# schematic.net
KiCad netlist of a schematic drawn in EAGLE
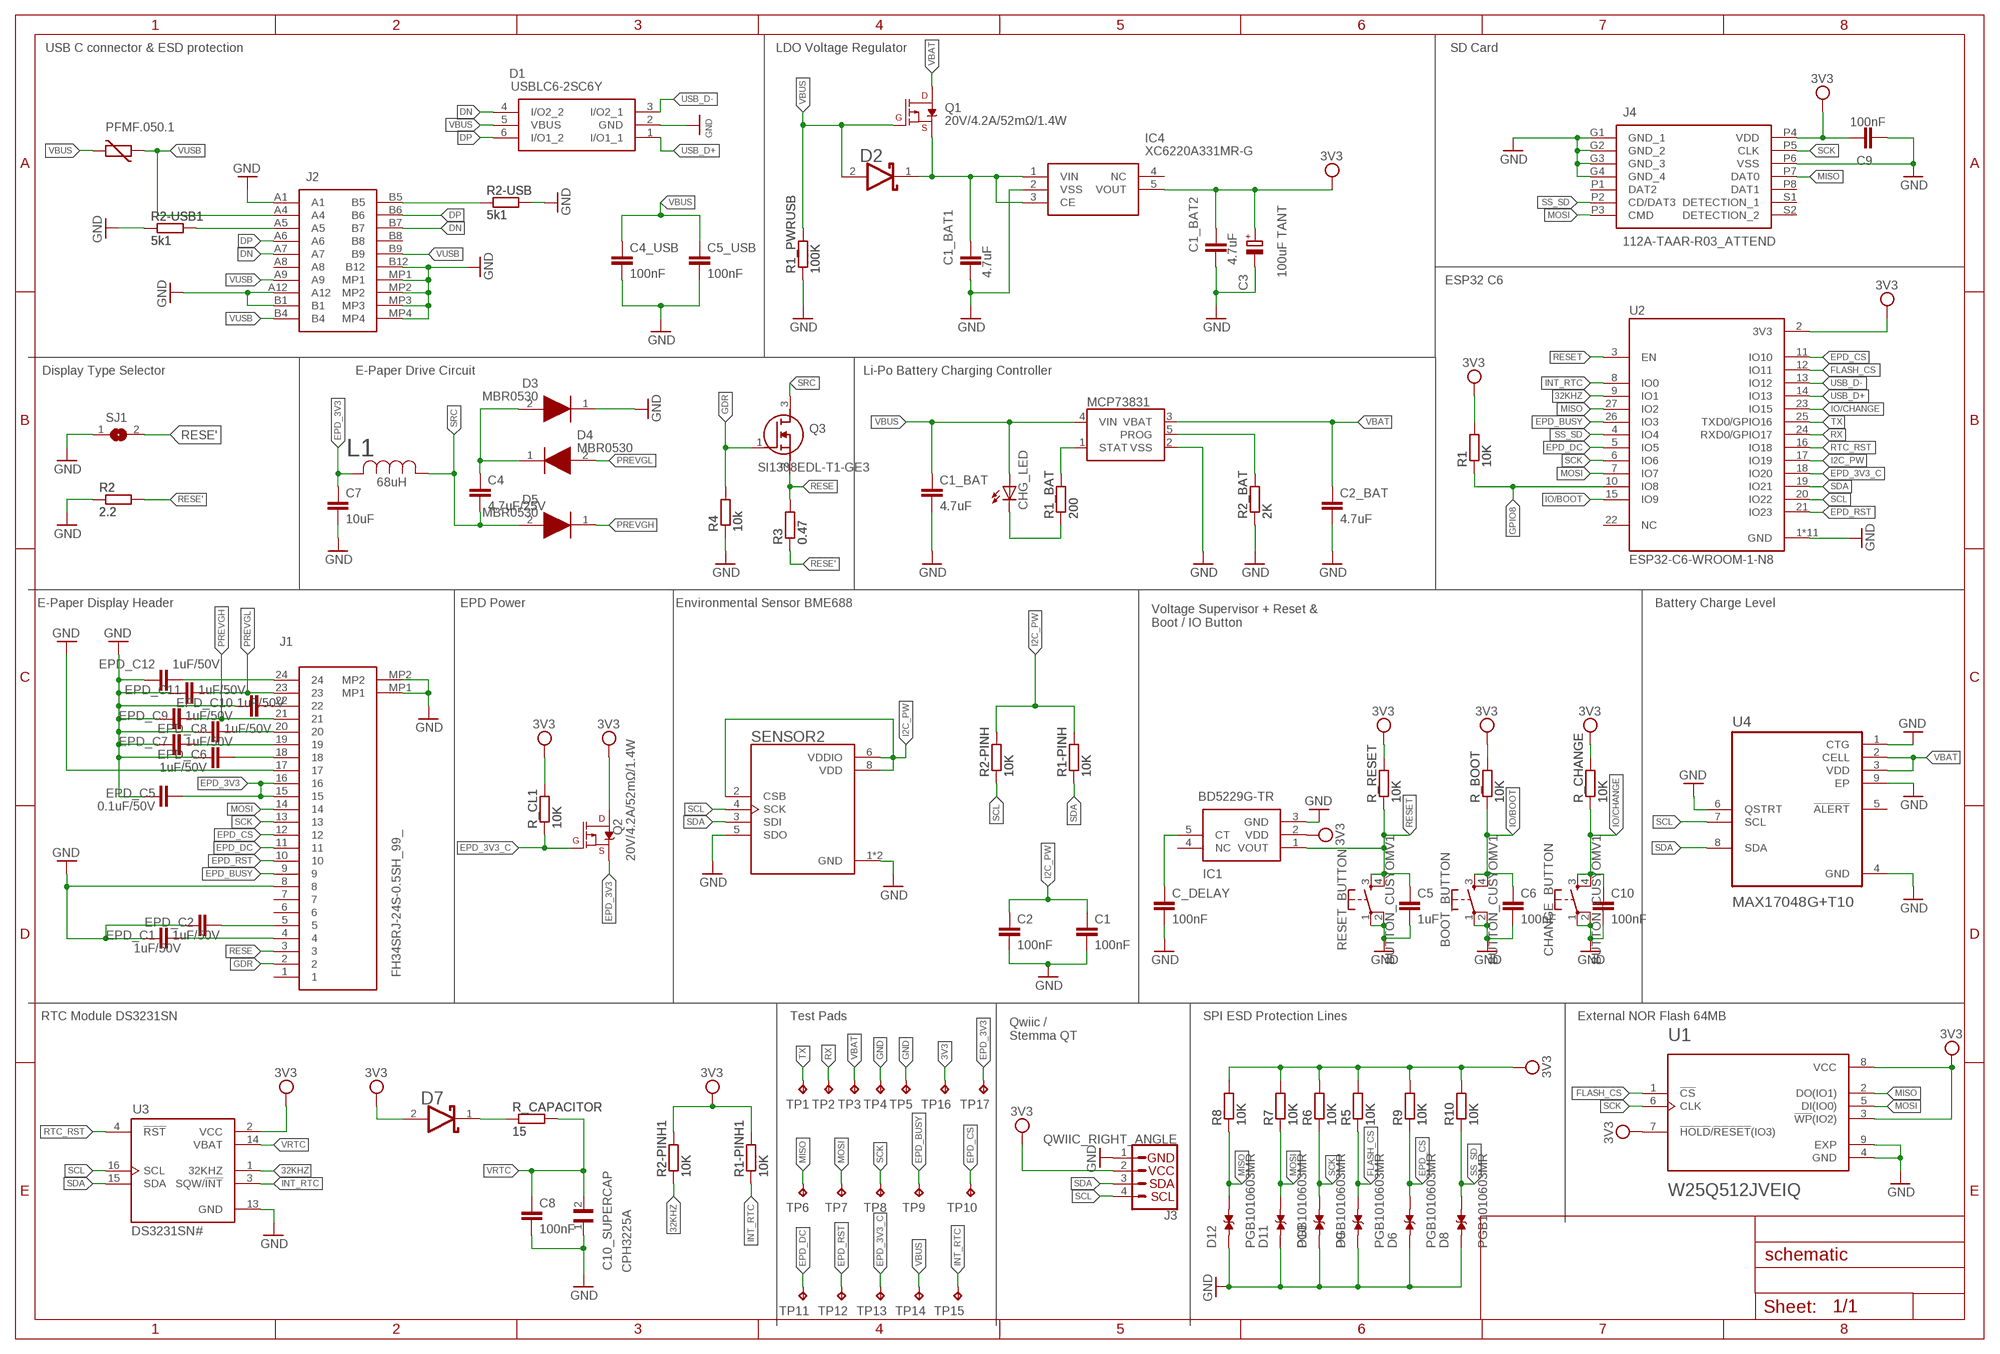
[diagram p0: schematic, sheet 1]

(export (version "E")
  (design (tool "Eeschema 10.0.6"))
  (components
    (comp (ref "BOOT_BUTTON")
      (value "BUTTON_CUSYOMV1")
      (footprint "eagle-import:MYBUTTON")
      (libsource (lib "eagle-import") (part "BUTTON_CUSYOMV1"))
    )
    (comp (ref "C1")
      (value "100nF")
      (footprint "eagle-import:ESP32_WROVER_EAGLE-LTSPICE_C0402")
      (libsource (lib "eagle-import") (part "ESP32_WROVER_EAGLE-LTSPICE_CC0402"))
    )
    (comp (ref "C1_BAT")
      (value "4.7uF")
      (footprint "eagle-import:ESP32_WROVER_EAGLE-LTSPICE_C0402")
      (libsource (lib "eagle-import") (part "ESP32_WROVER_EAGLE-LTSPICE_CC0402"))
    )
    (comp (ref "C1_BAT1")
      (value "4.7uF")
      (footprint "eagle-import:ESP32_WROVER_EAGLE-LTSPICE_C0402")
      (libsource (lib "eagle-import") (part "EAGLE-LTSPICE_CC0402"))
    )
    (comp (ref "C1_BAT2")
      (value "4.7uF")
      (footprint "eagle-import:ESP32_WROVER_EAGLE-LTSPICE_C0402")
      (libsource (lib "eagle-import") (part "EAGLE-LTSPICE_CC0402"))
    )
    (comp (ref "C2")
      (value "100nF")
      (footprint "eagle-import:ESP32_WROVER_EAGLE-LTSPICE_C0402")
      (libsource (lib "eagle-import") (part "ESP32_WROVER_EAGLE-LTSPICE_CC0402"))
    )
    (comp (ref "C2_BAT")
      (value "4.7uF")
      (footprint "eagle-import:ESP32_WROVER_EAGLE-LTSPICE_C0402")
      (libsource (lib "eagle-import") (part "ESP32_WROVER_EAGLE-LTSPICE_CC0402"))
    )
    (comp (ref "C3")
      (value "100uF TANT")
      (footprint "eagle-import:RCL_CT3528")
      (libsource (lib "eagle-import") (part "RCL_CPOL-EUCT3528"))
    )
    (comp (ref "C4")
      (value "4.7uF/25V")
      (footprint "eagle-import:ESP32_WROVER_EAGLE-LTSPICE_C0402")
      (libsource (lib "eagle-import") (part "ESP32_WROVER_EAGLE-LTSPICE_CC0402"))
    )
    (comp (ref "C4_USB")
      (value "100nF")
      (footprint "eagle-import:ESP32_WROVER_EAGLE-LTSPICE_C0402")
      (libsource (lib "eagle-import") (part "ESP32_WROVER_EAGLE-LTSPICE_CC0402"))
    )
    (comp (ref "C5")
      (value "1uF")
      (footprint "eagle-import:ESP32_WROVER_EAGLE-LTSPICE_C0402")
      (libsource (lib "eagle-import") (part "ESP32_WROVER_EAGLE-LTSPICE_CC0402"))
    )
    (comp (ref "C5_USB")
      (value "100nF")
      (footprint "eagle-import:ESP32_WROVER_EAGLE-LTSPICE_C0402")
      (libsource (lib "eagle-import") (part "ESP32_WROVER_EAGLE-LTSPICE_CC0402"))
    )
    (comp (ref "C6")
      (value "100nF")
      (footprint "eagle-import:ESP32_WROVER_EAGLE-LTSPICE_C0402")
      (libsource (lib "eagle-import") (part "ESP32_WROVER_EAGLE-LTSPICE_CC0402"))
    )
    (comp (ref "C7")
      (value "10uF")
      (footprint "eagle-import:ESP32_WROVER_EAGLE-LTSPICE_C0402")
      (libsource (lib "eagle-import") (part "ESP32_WROVER_EAGLE-LTSPICE_CC0402"))
    )
    (comp (ref "C8")
      (value "100nF")
      (footprint "eagle-import:ESP32_WROVER_EAGLE-LTSPICE_C0402")
      (libsource (lib "eagle-import") (part "ESP32_WROVER_EAGLE-LTSPICE_CC0402"))
    )
    (comp (ref "C9")
      (value "100nF")
      (footprint "eagle-import:ESP32_WROVER_EAGLE-LTSPICE_C0402")
      (libsource (lib "eagle-import") (part "EAGLE-LTSPICE_CC0402"))
    )
    (comp (ref "C10")
      (value "100nF")
      (footprint "eagle-import:ESP32_WROVER_EAGLE-LTSPICE_C0402")
      (libsource (lib "eagle-import") (part "ESP32_WROVER_EAGLE-LTSPICE_CC0402"))
    )
    (comp (ref "C10_SUPERCAP")
      (value "CPH3225A")
      (footprint "eagle-import:CAPCP3225X100N")
      (fields (field (name "MF") "Seiko Instruments"))
      (libsource (lib "eagle-import") (part "CPH3225A"))
    )
    (comp (ref "CHANGE_BUTTON")
      (value "BUTTON_CUSYOMV1")
      (footprint "eagle-import:MYBUTTON")
      (libsource (lib "eagle-import") (part "BUTTON_CUSYOMV1"))
    )
    (comp (ref "CHG_LED")
      (value "ADAFRUIT_LEDCHIP-LED0603")
      (footprint "eagle-import:ADAFRUIT_CHIP-LED0603")
      (libsource (lib "eagle-import") (part "ADAFRUIT_LEDCHIP-LED0603"))
    )
    (comp (ref "C_DELAY")
      (value "100nF")
      (footprint "eagle-import:ESP32_WROVER_EAGLE-LTSPICE_C0402")
      (libsource (lib "eagle-import") (part "ESP32_WROVER_EAGLE-LTSPICE_CC0402"))
    )
    (comp (ref "D1")
      (value "USBLC6-2SC6Y")
      (footprint "eagle-import:SOT95P280X145-6N")
      (fields (field (name "MF") "STMicroelectronics"))
      (libsource (lib "eagle-import") (part "USBLC6-2SC6Y"))
    )
    (comp (ref "D2")
      (value "ESP32_WROVER_AVX---SD0805S020S1R0_AVX_SD0805S020S1R0_0_0AVX_SD0805S020S1R0_0_0")
      (footprint "eagle-import:ESP32_WROVER_AVX---SD0805S020S1R0_AVX_SD0805S020S1R0_0")
      (fields
        (field (name "DIGIKEY_PART_NUMBER") "478-7800-1-ND")
        (field (name "MF") "AVX")
        (field (name "MOUSER_PART_NUMBER") "581-SD0805S020S1R0")
      )
      (libsource (lib "eagle-import") (part "ESP32_WROVER_AVX---SD0805S020S1R0_AVX_SD0805S020S1R0_0_0AVX_SD0805S020S1R0_0_0"))
    )
    (comp (ref "D3")
      (value "MBR0530")
      (footprint "eagle-import:SOD3716X135N")
      (fields (field (name "MF") "ON Semiconductor"))
      (libsource (lib "eagle-import") (part "MBR0530"))
    )
    (comp (ref "D4")
      (value "MBR0530")
      (footprint "eagle-import:SOD3716X135N")
      (fields (field (name "MF") "ON Semiconductor"))
      (libsource (lib "eagle-import") (part "MBR0530"))
    )
    (comp (ref "D5")
      (value "MBR0530")
      (footprint "eagle-import:SOD3716X135N")
      (fields (field (name "MF") "ON Semiconductor"))
      (libsource (lib "eagle-import") (part "MBR0530"))
    )
    (comp (ref "D6")
      (value "PGB1010603MR")
      (footprint "eagle-import:DIOC1608X36N")
      (fields (field (name "MF") "Littelfuse Inc."))
      (libsource (lib "eagle-import") (part "PGB1010603MR"))
    )
    (comp (ref "D7")
      (value "ESP32_WROVER_AVX---SD0805S020S1R0_AVX_SD0805S020S1R0_0_0AVX_SD0805S020S1R0_0_0")
      (footprint "eagle-import:ESP32_WROVER_AVX---SD0805S020S1R0_AVX_SD0805S020S1R0_0")
      (fields
        (field (name "DIGIKEY_PART_NUMBER") "478-7800-1-ND")
        (field (name "MF") "AVX")
        (field (name "MOUSER_PART_NUMBER") "581-SD0805S020S1R0")
      )
      (libsource (lib "eagle-import") (part "ESP32_WROVER_AVX---SD0805S020S1R0_AVX_SD0805S020S1R0_0_0AVX_SD0805S020S1R0_0_0"))
    )
    (comp (ref "D8")
      (value "PGB1010603MR")
      (footprint "eagle-import:DIOC1608X36N")
      (fields (field (name "MF") "Littelfuse Inc."))
      (libsource (lib "eagle-import") (part "PGB1010603MR"))
    )
    (comp (ref "D9")
      (value "PGB1010603MR")
      (footprint "eagle-import:DIOC1608X36N")
      (fields (field (name "MF") "Littelfuse Inc."))
      (libsource (lib "eagle-import") (part "PGB1010603MR"))
    )
    (comp (ref "D10")
      (value "PGB1010603MR")
      (footprint "eagle-import:DIOC1608X36N")
      (fields (field (name "MF") "Littelfuse Inc."))
      (libsource (lib "eagle-import") (part "PGB1010603MR"))
    )
    (comp (ref "D11")
      (value "PGB1010603MR")
      (footprint "eagle-import:DIOC1608X36N")
      (fields (field (name "MF") "Littelfuse Inc."))
      (libsource (lib "eagle-import") (part "PGB1010603MR"))
    )
    (comp (ref "D12")
      (value "PGB1010603MR")
      (footprint "eagle-import:DIOC1608X36N")
      (fields (field (name "MF") "Littelfuse Inc."))
      (libsource (lib "eagle-import") (part "PGB1010603MR"))
    )
    (comp (ref "EPD_C1")
      (value "1uF/50V")
      (footprint "eagle-import:ESP32_WROVER_EAGLE-LTSPICE_C0402")
      (libsource (lib "eagle-import") (part "ESP32_WROVER_EAGLE-LTSPICE_CC0402"))
    )
    (comp (ref "EPD_C2")
      (value "1uF/50V")
      (footprint "eagle-import:ESP32_WROVER_EAGLE-LTSPICE_C0402")
      (libsource (lib "eagle-import") (part "ESP32_WROVER_EAGLE-LTSPICE_CC0402"))
    )
    (comp (ref "EPD_C5")
      (value "0.1uF/50V")
      (footprint "eagle-import:ESP32_WROVER_EAGLE-LTSPICE_C0402")
      (libsource (lib "eagle-import") (part "ESP32_WROVER_EAGLE-LTSPICE_CC0402"))
    )
    (comp (ref "EPD_C6")
      (value "1uF/50V")
      (footprint "eagle-import:ESP32_WROVER_EAGLE-LTSPICE_C0402")
      (libsource (lib "eagle-import") (part "ESP32_WROVER_EAGLE-LTSPICE_CC0402"))
    )
    (comp (ref "EPD_C7")
      (value "1uF/50V")
      (footprint "eagle-import:ESP32_WROVER_EAGLE-LTSPICE_C0402")
      (libsource (lib "eagle-import") (part "ESP32_WROVER_EAGLE-LTSPICE_CC0402"))
    )
    (comp (ref "EPD_C8")
      (value "1uF/50V")
      (footprint "eagle-import:ESP32_WROVER_EAGLE-LTSPICE_C0402")
      (libsource (lib "eagle-import") (part "ESP32_WROVER_EAGLE-LTSPICE_CC0402"))
    )
    (comp (ref "EPD_C9")
      (value "1uF/50V")
      (footprint "eagle-import:ESP32_WROVER_EAGLE-LTSPICE_C0402")
      (libsource (lib "eagle-import") (part "ESP32_WROVER_EAGLE-LTSPICE_CC0402"))
    )
    (comp (ref "EPD_C10")
      (value "1uF/50V")
      (footprint "eagle-import:ESP32_WROVER_EAGLE-LTSPICE_C0402")
      (libsource (lib "eagle-import") (part "ESP32_WROVER_EAGLE-LTSPICE_CC0402"))
    )
    (comp (ref "EPD_C11")
      (value "1uF/50V")
      (footprint "eagle-import:ESP32_WROVER_EAGLE-LTSPICE_C0402")
      (libsource (lib "eagle-import") (part "ESP32_WROVER_EAGLE-LTSPICE_CC0402"))
    )
    (comp (ref "EPD_C12")
      (value "1uF/50V")
      (footprint "eagle-import:ESP32_WROVER_EAGLE-LTSPICE_C0402")
      (libsource (lib "eagle-import") (part "ESP32_WROVER_EAGLE-LTSPICE_CC0402"))
    )
    (comp (ref "IC1")
      (value "BD5229G-TR")
      (footprint "eagle-import:SOT95P280X125-5N")
      (fields (field (name "MOUSER_PART_NUMBER") "755-BD5229G-TR"))
      (libsource (lib "eagle-import") (part "BD5229G-TR"))
    )
    (comp (ref "IC4")
      (value "XC6220A331MR-G")
      (footprint "eagle-import:SOT95P280X120-5N")
      (fields (field (name "MOUSER_PART_NUMBER") "865-XC6220A331MR-G"))
      (libsource (lib "eagle-import") (part "XC6220A331MR-G"))
    )
    (comp (ref "J1")
      (value "FH34SRJ-24S-0.5SH_99_")
      (footprint "eagle-import:FH34SRJ24S05SH99")
      (fields
        (field (name "MANUFACTURER_PART_NUMBER") "FH34SRJ-24S-0.5SH(99)")
        (field (name "MOUSER_PART_NUMBER") "798-FH34SRJ24S05SH99")
      )
      (libsource (lib "eagle-import") (part "FH34SRJ-24S-0.5SH_99_"))
    )
    (comp (ref "J2")
      (value "SAMACSYS_PARTS_USB4110-GF-A")
      (footprint "eagle-import:SAMACSYS_PARTS_USB4110GFA")
      (fields
        (field (name "MANUFACTURER_PART_NUMBER") "USB4110-GF-A")
        (field (name "MOUSER_PART_NUMBER") "640-USB4110-GF-A")
      )
      (libsource (lib "eagle-import") (part "SAMACSYS_PARTS_USB4110-GF-A"))
    )
    (comp (ref "J3")
      (value "QWIIC_RIGHT_ANGLE")
      (footprint "eagle-import:JST04_1MM_RA")
      (libsource (lib "eagle-import") (part "QWIIC_CONNECTORJS-1MM"))
    )
    (comp (ref "J4")
      (value "112A-TAAR-R03_ATTEND")
      (footprint "eagle-import:112ATAARR03ATTEND")
      (fields (field (name "MANUFACTURER_PART_NUMBER") "112A-TAAR-R03 ATTEND"))
      (libsource (lib "eagle-import") (part "112A-TAAR-R03_ATTEND"))
    )
    (comp (ref "L1")
      (value "744043680IND_4828-WE-TPC_WRE")
      (footprint "eagle-import:IND_4828-WE-TPC_WRE")
      (fields
        (field (name "MANUFACTURER_PART_NUMBER") "744043680")
        (field (name "VALUE_V") "68uH")
        (field (name "COPYRIGHT") "Copyright (C) 2024 Ultra Librarian. All rights reserved.")
      )
      (libsource (lib "eagle-import") (part "744043680IND_4828-WE-TPC_WRE"))
    )
    (comp (ref "MCP73831")
      (value "ESP32_WROVER_SPARKFUN-IC-POWER_MCP73831")
      (footprint "eagle-import:ESP32_WROVER_SPARKFUN-IC-POWER_SOT23-5")
      (libsource (lib "eagle-import") (part "ESP32_WROVER_SPARKFUN-IC-POWER_MCP73831"))
    )
    (comp (ref "PFMF.050.1")
      (value "ESP32C6_VARISTORCN1812")
      (footprint "eagle-import:ESP32C6_VARISTOR_CT_CN1812")
      (libsource (lib "eagle-import") (part "ESP32C6_VARISTORCN1812"))
    )
    (comp (ref "Q1")
      (value "20V/4.2A/52mΩ/1.4W")
      (footprint "eagle-import:ESP32_WROVER_SPARKFUN-DISCRETESEMI_SOT23-3")
      (libsource (lib "eagle-import") (part "ESP32_WROVER_SPARKFUN-DISCRETESEMI_MOSFET_PCH-DMG2305UX-7"))
    )
    (comp (ref "Q2")
      (value "20V/4.2A/52mΩ/1.4W")
      (footprint "eagle-import:ESP32_WROVER_SPARKFUN-DISCRETESEMI_SOT23-3")
      (libsource (lib "eagle-import") (part "ESP32_WROVER_SPARKFUN-DISCRETESEMI_MOSFET_PCH-DMG2305UX-7"))
    )
    (comp (ref "Q3")
      (value "SI1308EDL-T1-GE3")
      (footprint "eagle-import:SOT65P210X110-3N")
      (fields (field (name "MF") "Vishay Siliconix"))
      (libsource (lib "eagle-import") (part "SI1308EDL-T1-GE3"))
    )
    (comp (ref "R1")
      (value "10K")
      (footprint "eagle-import:ESP32_WROVER_EAGLE-LTSPICE_R0402")
      (libsource (lib "eagle-import") (part "ESP32_WROVER_EAGLE-LTSPICE_RR0402"))
    )
    (comp (ref "R1-PINH")
      (value "10K")
      (footprint "eagle-import:ESP32_WROVER_EAGLE-LTSPICE_R0402")
      (libsource (lib "eagle-import") (part "ESP32_WROVER_EAGLE-LTSPICE_RR0402"))
    )
    (comp (ref "R1-PINH1")
      (value "10K")
      (footprint "eagle-import:ESP32_WROVER_EAGLE-LTSPICE_R0402")
      (libsource (lib "eagle-import") (part "ESP32_WROVER_EAGLE-LTSPICE_RR0402"))
    )
    (comp (ref "R1_BAT")
      (value "200")
      (footprint "eagle-import:ESP32_WROVER_EAGLE-LTSPICE_R0402")
      (libsource (lib "eagle-import") (part "ESP32_WROVER_EAGLE-LTSPICE_RR0402"))
    )
    (comp (ref "R1_PWRUSB")
      (value "100K")
      (footprint "eagle-import:ESP32_WROVER_EAGLE-LTSPICE_R0402")
      (libsource (lib "eagle-import") (part "ESP32_WROVER_EAGLE-LTSPICE_RR0402"))
    )
    (comp (ref "R2")
      (value "2.2")
      (footprint "eagle-import:ESP32_WROVER_EAGLE-LTSPICE_R0402")
      (libsource (lib "eagle-import") (part "ESP32_WROVER_EAGLE-LTSPICE_RR0402"))
    )
    (comp (ref "R2-PINH")
      (value "10K")
      (footprint "eagle-import:ESP32_WROVER_EAGLE-LTSPICE_R0402")
      (libsource (lib "eagle-import") (part "ESP32_WROVER_EAGLE-LTSPICE_RR0402"))
    )
    (comp (ref "R2-PINH1")
      (value "10K")
      (footprint "eagle-import:ESP32_WROVER_EAGLE-LTSPICE_R0402")
      (libsource (lib "eagle-import") (part "ESP32_WROVER_EAGLE-LTSPICE_RR0402"))
    )
    (comp (ref "R2-USB")
      (value "5k1")
      (footprint "eagle-import:ESP32_WROVER_EAGLE-LTSPICE_R0402")
      (libsource (lib "eagle-import") (part "ESP32_WROVER_EAGLE-LTSPICE_RR0402"))
    )
    (comp (ref "R2-USB1")
      (value "5k1")
      (footprint "eagle-import:ESP32_WROVER_EAGLE-LTSPICE_R0402")
      (libsource (lib "eagle-import") (part "ESP32_WROVER_EAGLE-LTSPICE_RR0402"))
    )
    (comp (ref "R2_BAT")
      (value "2K")
      (footprint "eagle-import:ESP32_WROVER_EAGLE-LTSPICE_R0402")
      (libsource (lib "eagle-import") (part "ESP32_WROVER_EAGLE-LTSPICE_RR0402"))
    )
    (comp (ref "R3")
      (value "0.47")
      (footprint "eagle-import:ESP32_WROVER_EAGLE-LTSPICE_R0402")
      (libsource (lib "eagle-import") (part "ESP32_WROVER_EAGLE-LTSPICE_RR0402"))
    )
    (comp (ref "R4")
      (value "10k")
      (footprint "eagle-import:ESP32_WROVER_EAGLE-LTSPICE_R0402")
      (libsource (lib "eagle-import") (part "ESP32_WROVER_EAGLE-LTSPICE_RR0402"))
    )
    (comp (ref "R5")
      (value "10K")
      (footprint "eagle-import:ESP32_WROVER_EAGLE-LTSPICE_R0402")
      (libsource (lib "eagle-import") (part "ESP32_WROVER_EAGLE-LTSPICE_RR0402"))
    )
    (comp (ref "R6")
      (value "10K")
      (footprint "eagle-import:ESP32_WROVER_EAGLE-LTSPICE_R0402")
      (libsource (lib "eagle-import") (part "ESP32_WROVER_EAGLE-LTSPICE_RR0402"))
    )
    (comp (ref "R7")
      (value "10K")
      (footprint "eagle-import:ESP32_WROVER_EAGLE-LTSPICE_R0402")
      (libsource (lib "eagle-import") (part "ESP32_WROVER_EAGLE-LTSPICE_RR0402"))
    )
    (comp (ref "R8")
      (value "10K")
      (footprint "eagle-import:ESP32_WROVER_EAGLE-LTSPICE_R0402")
      (libsource (lib "eagle-import") (part "ESP32_WROVER_EAGLE-LTSPICE_RR0402"))
    )
    (comp (ref "R9")
      (value "10K")
      (footprint "eagle-import:ESP32_WROVER_EAGLE-LTSPICE_R0402")
      (libsource (lib "eagle-import") (part "ESP32_WROVER_EAGLE-LTSPICE_RR0402"))
    )
    (comp (ref "R10")
      (value "10K")
      (footprint "eagle-import:ESP32_WROVER_EAGLE-LTSPICE_R0402")
      (libsource (lib "eagle-import") (part "ESP32_WROVER_EAGLE-LTSPICE_RR0402"))
    )
    (comp (ref "RESET_BUTTON")
      (value "BUTTON_CUSYOMV1")
      (footprint "eagle-import:MYBUTTON")
      (libsource (lib "eagle-import") (part "BUTTON_CUSYOMV1"))
    )
    (comp (ref "R_BOOT")
      (value "10K")
      (footprint "eagle-import:ESP32_WROVER_EAGLE-LTSPICE_R0402")
      (libsource (lib "eagle-import") (part "ESP32_WROVER_EAGLE-LTSPICE_RR0402"))
    )
    (comp (ref "R_CAPACITOR")
      (value "15")
      (footprint "eagle-import:ESP32_WROVER_EAGLE-LTSPICE_R0402")
      (libsource (lib "eagle-import") (part "ESP32_WROVER_EAGLE-LTSPICE_RR0402"))
    )
    (comp (ref "R_CHANGE")
      (value "10K")
      (footprint "eagle-import:ESP32_WROVER_EAGLE-LTSPICE_R0402")
      (libsource (lib "eagle-import") (part "ESP32_WROVER_EAGLE-LTSPICE_RR0402"))
    )
    (comp (ref "R_CL1")
      (value "10K")
      (footprint "eagle-import:ESP32_WROVER_EAGLE-LTSPICE_R0402")
      (libsource (lib "eagle-import") (part "ESP32_WROVER_EAGLE-LTSPICE_RR0402"))
    )
    (comp (ref "R_RESET")
      (value "10K")
      (footprint "eagle-import:ESP32_WROVER_EAGLE-LTSPICE_R0402")
      (libsource (lib "eagle-import") (part "ESP32_WROVER_EAGLE-LTSPICE_RR0402"))
    )
    (comp (ref "SENSOR2")
      (value "ESP32_WROVER_BME680_BME680")
      (footprint "eagle-import:ESP32_WROVER_BME680_PSON80P300X300X100-8N")
      (fields (field (name "MF") "Bosch Sensortec") (field (name "MP") "BME680"))
      (libsource (lib "eagle-import") (part "ESP32_WROVER_BME680_BME680"))
    )
    (comp (ref "SJ1") (value "SJ") (footprint "eagle-import:SJ") (libsource (lib "eagle-import") (part "SJ")))
    (comp (ref "TP1")
      (value "TPTP20R")
      (footprint "eagle-import:TP20R")
      (libsource (lib "eagle-import") (part "TPTP20R"))
    )
    (comp (ref "TP2")
      (value "TPTP20R")
      (footprint "eagle-import:TP20R")
      (libsource (lib "eagle-import") (part "TPTP20R"))
    )
    (comp (ref "TP3")
      (value "TPTP20R")
      (footprint "eagle-import:TP20R")
      (libsource (lib "eagle-import") (part "TPTP20R"))
    )
    (comp (ref "TP4")
      (value "TPTP20R")
      (footprint "eagle-import:TP20R")
      (libsource (lib "eagle-import") (part "TPTP20R"))
    )
    (comp (ref "TP5")
      (value "TPTP20R")
      (footprint "eagle-import:TP20R")
      (libsource (lib "eagle-import") (part "TPTP20R"))
    )
    (comp (ref "TP6")
      (value "TPTP20R")
      (footprint "eagle-import:TP20R")
      (libsource (lib "eagle-import") (part "TPTP20R"))
    )
    (comp (ref "TP7")
      (value "TPTP20R")
      (footprint "eagle-import:TP20R")
      (libsource (lib "eagle-import") (part "TPTP20R"))
    )
    (comp (ref "TP8")
      (value "TPTP20R")
      (footprint "eagle-import:TP20R")
      (libsource (lib "eagle-import") (part "TPTP20R"))
    )
    (comp (ref "TP9")
      (value "TPTP20R")
      (footprint "eagle-import:TP20R")
      (libsource (lib "eagle-import") (part "TPTP20R"))
    )
    (comp (ref "TP10")
      (value "TPTP20R")
      (footprint "eagle-import:TP20R")
      (libsource (lib "eagle-import") (part "TPTP20R"))
    )
    (comp (ref "TP11")
      (value "TPTP20R")
      (footprint "eagle-import:TP20R")
      (libsource (lib "eagle-import") (part "TPTP20R"))
    )
    (comp (ref "TP12")
      (value "TPTP20R")
      (footprint "eagle-import:TP20R")
      (libsource (lib "eagle-import") (part "TPTP20R"))
    )
    (comp (ref "TP13")
      (value "TPTP20R")
      (footprint "eagle-import:TP20R")
      (libsource (lib "eagle-import") (part "TPTP20R"))
    )
    (comp (ref "TP14")
      (value "TPTP20R")
      (footprint "eagle-import:TP20R")
      (libsource (lib "eagle-import") (part "TPTP20R"))
    )
    (comp (ref "TP15")
      (value "TPTP20R")
      (footprint "eagle-import:TP20R")
      (libsource (lib "eagle-import") (part "TPTP20R"))
    )
    (comp (ref "TP16")
      (value "TPTP20R")
      (footprint "eagle-import:TP20R")
      (libsource (lib "eagle-import") (part "TPTP20R"))
    )
    (comp (ref "TP17")
      (value "TPTP20R")
      (footprint "eagle-import:TP20R")
      (libsource (lib "eagle-import") (part "TPTP20R"))
    )
    (comp (ref "U1")
      (value "W25Q512JVEIQ")
      (footprint "eagle-import:SON127P600X800X80-9N")
      (fields (field (name "MF") "Winbond Electronics"))
      (libsource (lib "eagle-import") (part "W25Q512JVEIQ"))
    )
    (comp (ref "U2")
      (value "ESP32-C6-WROOM-1-N8")
      (footprint "eagle-import:XCVR_ESP32-C6-WROOM-1-N8")
      (fields (field (name "MF") "Espressif Systems"))
      (libsource (lib "eagle-import") (part "ESP32-C6-WROOM-1-N8"))
    )
    (comp (ref "U3")
      (value "DS3231SN#")
      (footprint "eagle-import:SOIC127P1032X265-16N")
      (fields (field (name "MF") "Analog Devices"))
      (libsource (lib "eagle-import") (part "DS3231SN#"))
    )
    (comp (ref "U4")
      (value "MAX17048G+T10")
      (footprint "eagle-import:SON50P200X200X80-9N")
      (fields (field (name "MF") "Analog Devices"))
      (libsource (lib "eagle-import") (part "MAX17048G+T10"))
    )
  )
  (nets
    (net (code "1") (name "3V3") (class "Default")
      (node (ref "C1_BAT2") (pin "1") (pinfunction "1_1") (pintype "passive"))
      (node (ref "C3") (pin "+") (pinfunction "+_+") (pintype "passive"))
      (node (ref "C9") (pin "1") (pinfunction "1_1") (pintype "passive"))
      (node (ref "D7") (pin "2") (pinfunction "ANODE_2") (pintype "bidirectional"))
      (node (ref "IC1") (pin "2") (pinfunction "VDD_2") (pintype "bidirectional"))
      (node (ref "IC4") (pin "5") (pinfunction "VOUT_5") (pintype "bidirectional"))
      (node (ref "J3") (pin "2") (pinfunction "2_2") (pintype "power_in"))
      (node (ref "J4") (pin "P4") (pinfunction "VDD_P4") (pintype "bidirectional"))
      (node (ref "Q2") (pin "3") (pinfunction "D_3") (pintype "bidirectional"))
      (node (ref "R1") (pin "2") (pinfunction "2_2") (pintype "passive"))
      (node (ref "R1-PINH1") (pin "2") (pinfunction "2_2") (pintype "passive"))
      (node (ref "R10") (pin "2") (pinfunction "2_2") (pintype "passive"))
      (node (ref "R2-PINH1") (pin "2") (pinfunction "2_2") (pintype "passive"))
      (node (ref "R5") (pin "2") (pinfunction "2_2") (pintype "passive"))
      (node (ref "R6") (pin "2") (pinfunction "2_2") (pintype "passive"))
      (node (ref "R7") (pin "2") (pinfunction "2_2") (pintype "passive"))
      (node (ref "R8") (pin "2") (pinfunction "2_2") (pintype "passive"))
      (node (ref "R9") (pin "2") (pinfunction "2_2") (pintype "passive"))
      (node (ref "R_BOOT") (pin "2") (pinfunction "2_2") (pintype "passive"))
      (node (ref "R_CHANGE") (pin "2") (pinfunction "2_2") (pintype "passive"))
      (node (ref "R_CL1") (pin "2") (pinfunction "2_2") (pintype "passive"))
      (node (ref "R_RESET") (pin "2") (pinfunction "2_2") (pintype "passive"))
      (node (ref "TP16") (pin "TP") (pinfunction "TP_TP") (pintype "input"))
      (node (ref "U1") (pin "3") (pinfunction "~{WP}(IO2)_3") (pintype "bidirectional"))
      (node (ref "U1") (pin "7") (pinfunction "~{HOLD}/~{RESET}(IO3)_7") (pintype "bidirectional"))
      (node (ref "U1") (pin "8") (pinfunction "VCC_8") (pintype "power_in"))
      (node (ref "U2") (pin "2") (pinfunction "3V3_2") (pintype "power_in"))
      (node (ref "U3") (pin "2") (pinfunction "VCC_2") (pintype "power_in"))
    )
    (net (code "2") (name "32KHZ") (class "Default")
      (node (ref "R2-PINH1") (pin "1") (pinfunction "1_1") (pintype "passive"))
      (node (ref "U2") (pin "9") (pinfunction "IO1_9") (pintype "bidirectional"))
      (node (ref "U3") (pin "1") (pinfunction "32KHZ_1") (pintype "output"))
    )
    (net (code "3") (name "DN") (class "Default")
      (node (ref "D1") (pin "4") (pinfunction "I/O2_2_4") (pintype "bidirectional"))
      (node (ref "J2") (pin "A7") (pinfunction "A7_A7") (pintype "bidirectional"))
      (node (ref "J2") (pin "B7") (pinfunction "B7_B7") (pintype "bidirectional"))
    )
    (net (code "4") (name "DP") (class "Default")
      (node (ref "D1") (pin "6") (pinfunction "I/O1_2_6") (pintype "bidirectional"))
      (node (ref "J2") (pin "A6") (pinfunction "A6_A6") (pintype "bidirectional"))
      (node (ref "J2") (pin "B6") (pinfunction "B6_B6") (pintype "bidirectional"))
    )
    (net (code "5") (name "EPD_3V3") (class "Default")
      (node (ref "C7") (pin "1") (pinfunction "1_1") (pintype "passive"))
      (node (ref "EPD_C5") (pin "2") (pinfunction "2_2") (pintype "passive"))
      (node (ref "J1") (pin "15") (pinfunction "15_15") (pintype "bidirectional"))
      (node (ref "J1") (pin "16") (pinfunction "16_16") (pintype "bidirectional"))
      (node (ref "L1") (pin "2") (pinfunction "2_2") (pintype "passive"))
      (node (ref "Q2") (pin "2") (pinfunction "S_2") (pintype "bidirectional"))
      (node (ref "TP17") (pin "TP") (pinfunction "TP_TP") (pintype "input"))
    )
    (net (code "6") (name "EPD_3V3_C") (class "Default")
      (node (ref "Q2") (pin "1") (pinfunction "G_1") (pintype "bidirectional"))
      (node (ref "R_CL1") (pin "1") (pinfunction "1_1") (pintype "passive"))
      (node (ref "TP13") (pin "TP") (pinfunction "TP_TP") (pintype "input"))
      (node (ref "U2") (pin "18") (pinfunction "IO20_18") (pintype "bidirectional"))
    )
    (net (code "7") (name "EPD_BUSY") (class "Default")
      (node (ref "J1") (pin "9") (pinfunction "9_9") (pintype "bidirectional"))
      (node (ref "TP9") (pin "TP") (pinfunction "TP_TP") (pintype "input"))
      (node (ref "U2") (pin "26") (pinfunction "IO3_26") (pintype "bidirectional"))
    )
    (net (code "8") (name "EPD_CS") (class "Default")
      (node (ref "D6") (pin "2") (pinfunction "2_2") (pintype "passive"))
      (node (ref "J1") (pin "12") (pinfunction "12_12") (pintype "bidirectional"))
      (node (ref "R9") (pin "1") (pinfunction "1_1") (pintype "passive"))
      (node (ref "TP10") (pin "TP") (pinfunction "TP_TP") (pintype "input"))
      (node (ref "U2") (pin "11") (pinfunction "IO10_11") (pintype "bidirectional"))
    )
    (net (code "9") (name "EPD_DC") (class "Default")
      (node (ref "J1") (pin "11") (pinfunction "11_11") (pintype "bidirectional"))
      (node (ref "TP11") (pin "TP") (pinfunction "TP_TP") (pintype "input"))
      (node (ref "U2") (pin "5") (pinfunction "IO5_5") (pintype "bidirectional"))
    )
    (net (code "10") (name "EPD_RST") (class "Default")
      (node (ref "J1") (pin "10") (pinfunction "10_10") (pintype "bidirectional"))
      (node (ref "TP12") (pin "TP") (pinfunction "TP_TP") (pintype "input"))
      (node (ref "U2") (pin "21") (pinfunction "IO23_21") (pintype "bidirectional"))
    )
    (net (code "11") (name "FLASH_CS") (class "Default")
      (node (ref "D9") (pin "2") (pinfunction "2_2") (pintype "passive"))
      (node (ref "R5") (pin "1") (pinfunction "1_1") (pintype "passive"))
      (node (ref "U1") (pin "1") (pinfunction "~{CS}_1") (pintype "input"))
      (node (ref "U2") (pin "12") (pinfunction "IO11_12") (pintype "bidirectional"))
    )
    (net (code "12") (name "GDR") (class "Default")
      (node (ref "J1") (pin "2") (pinfunction "2_2") (pintype "bidirectional"))
      (node (ref "Q3") (pin "1") (pinfunction "G_1") (pintype "bidirectional"))
      (node (ref "R4") (pin "2") (pinfunction "2_2") (pintype "passive"))
    )
    (net (code "13") (name "GND") (class "Default")
      (node (ref "BOOT_BUTTON") (pin "1") (pinfunction "1_1") (pintype "passive"))
      (node (ref "BOOT_BUTTON") (pin "2") (pinfunction "2_2") (pintype "passive"))
      (node (ref "C1") (pin "2") (pinfunction "2_2") (pintype "passive"))
      (node (ref "C10") (pin "2") (pinfunction "2_2") (pintype "passive"))
      (node (ref "C10_SUPERCAP") (pin "1") (pinfunction "1_1") (pintype "passive"))
      (node (ref "C1_BAT") (pin "2") (pinfunction "2_2") (pintype "passive"))
      (node (ref "C1_BAT1") (pin "2") (pinfunction "2_2") (pintype "passive"))
      (node (ref "C1_BAT2") (pin "2") (pinfunction "2_2") (pintype "passive"))
      (node (ref "C2") (pin "2") (pinfunction "2_2") (pintype "passive"))
      (node (ref "C2_BAT") (pin "2") (pinfunction "2_2") (pintype "passive"))
      (node (ref "C3") (pin "-") (pinfunction "-_-") (pintype "passive"))
      (node (ref "C4_USB") (pin "2") (pinfunction "2_2") (pintype "passive"))
      (node (ref "C5") (pin "2") (pinfunction "2_2") (pintype "passive"))
      (node (ref "C5_USB") (pin "2") (pinfunction "2_2") (pintype "passive"))
      (node (ref "C6") (pin "2") (pinfunction "2_2") (pintype "passive"))
      (node (ref "C7") (pin "2") (pinfunction "2_2") (pintype "passive"))
      (node (ref "C8") (pin "2") (pinfunction "2_2") (pintype "passive"))
      (node (ref "C9") (pin "2") (pinfunction "2_2") (pintype "passive"))
      (node (ref "CHANGE_BUTTON") (pin "1") (pinfunction "1_1") (pintype "passive"))
      (node (ref "CHANGE_BUTTON") (pin "2") (pinfunction "2_2") (pintype "passive"))
      (node (ref "C_DELAY") (pin "2") (pinfunction "2_2") (pintype "passive"))
      (node (ref "D1") (pin "2") (pinfunction "GND_2") (pintype "bidirectional"))
      (node (ref "D10") (pin "1") (pinfunction "1_1") (pintype "passive"))
      (node (ref "D11") (pin "1") (pinfunction "1_1") (pintype "passive"))
      (node (ref "D12") (pin "1") (pinfunction "1_1") (pintype "passive"))
      (node (ref "D3") (pin "1") (pinfunction "K_1") (pintype "bidirectional"))
      (node (ref "D6") (pin "1") (pinfunction "1_1") (pintype "passive"))
      (node (ref "D8") (pin "1") (pinfunction "1_1") (pintype "passive"))
      (node (ref "D9") (pin "1") (pinfunction "1_1") (pintype "passive"))
      (node (ref "EPD_C1") (pin "1") (pinfunction "1_1") (pintype "passive"))
      (node (ref "EPD_C10") (pin "1") (pinfunction "1_1") (pintype "passive"))
      (node (ref "EPD_C11") (pin "1") (pinfunction "1_1") (pintype "passive"))
      (node (ref "EPD_C12") (pin "1") (pinfunction "1_1") (pintype "passive"))
      (node (ref "EPD_C2") (pin "1") (pinfunction "1_1") (pintype "passive"))
      (node (ref "EPD_C5") (pin "1") (pinfunction "1_1") (pintype "passive"))
      (node (ref "EPD_C6") (pin "1") (pinfunction "1_1") (pintype "passive"))
      (node (ref "EPD_C7") (pin "1") (pinfunction "1_1") (pintype "passive"))
      (node (ref "EPD_C8") (pin "1") (pinfunction "1_1") (pintype "passive"))
      (node (ref "EPD_C9") (pin "1") (pinfunction "1_1") (pintype "passive"))
      (node (ref "IC1") (pin "3") (pinfunction "GND_3") (pintype "bidirectional"))
      (node (ref "IC4") (pin "2") (pinfunction "VSS_2") (pintype "bidirectional"))
      (node (ref "J1") (pin "17") (pinfunction "17_17") (pintype "bidirectional"))
      (node (ref "J1") (pin "8") (pinfunction "8_8") (pintype "bidirectional"))
      (node (ref "J1") (pin "MP1") (pinfunction "MP1_MP1") (pintype "bidirectional"))
      (node (ref "J1") (pin "MP2") (pinfunction "MP2_MP2") (pintype "bidirectional"))
      (node (ref "J2") (pin "A1") (pinfunction "A1_A1") (pintype "bidirectional"))
      (node (ref "J2") (pin "A12") (pinfunction "A12_A12") (pintype "bidirectional"))
      (node (ref "J2") (pin "B1") (pinfunction "B1_B1") (pintype "bidirectional"))
      (node (ref "J2") (pin "B12") (pinfunction "B12_B12") (pintype "bidirectional"))
      (node (ref "J2") (pin "MP1") (pinfunction "MP1_MP1") (pintype "bidirectional"))
      (node (ref "J2") (pin "MP2") (pinfunction "MP2_MP2") (pintype "bidirectional"))
      (node (ref "J2") (pin "MP3") (pinfunction "MP3_MP3") (pintype "bidirectional"))
      (node (ref "J2") (pin "MP4") (pinfunction "MP4_MP4") (pintype "bidirectional"))
      (node (ref "J3") (pin "1") (pinfunction "1_1") (pintype "power_in"))
      (node (ref "J4") (pin "G1") (pinfunction "GND_1_G1") (pintype "bidirectional"))
      (node (ref "J4") (pin "G2") (pinfunction "GND_2_G2") (pintype "bidirectional"))
      (node (ref "J4") (pin "G3") (pinfunction "GND_3_G3") (pintype "bidirectional"))
      (node (ref "J4") (pin "G4") (pinfunction "GND_4_G4") (pintype "bidirectional"))
      (node (ref "J4") (pin "P6") (pinfunction "VSS_P6") (pintype "bidirectional"))
      (node (ref "MCP73831") (pin "2") (pinfunction "VSS_2") (pintype "power_in"))
      (node (ref "R1_PWRUSB") (pin "1") (pinfunction "1_1") (pintype "passive"))
      (node (ref "R2") (pin "1") (pinfunction "1_1") (pintype "passive"))
      (node (ref "R2-USB") (pin "2") (pinfunction "2_2") (pintype "passive"))
      (node (ref "R2-USB1") (pin "1") (pinfunction "1_1") (pintype "passive"))
      (node (ref "R2_BAT") (pin "1") (pinfunction "1_1") (pintype "passive"))
      (node (ref "R4") (pin "1") (pinfunction "1_1") (pintype "passive"))
      (node (ref "RESET_BUTTON") (pin "1") (pinfunction "1_1") (pintype "passive"))
      (node (ref "RESET_BUTTON") (pin "2") (pinfunction "2_2") (pintype "passive"))
      (node (ref "SENSOR2") (pin "1") (pinfunction "GND_1") (pintype "power_in"))
      (node (ref "SENSOR2") (pin "5") (pinfunction "SDO_5") (pintype "bidirectional"))
      (node (ref "SENSOR2") (pin "7") (pinfunction "GND_7") (pintype "power_in"))
      (node (ref "SJ1") (pin "1") (pinfunction "1_1") (pintype "passive"))
      (node (ref "TP4") (pin "TP") (pinfunction "TP_TP") (pintype "input"))
      (node (ref "TP5") (pin "TP") (pinfunction "TP_TP") (pintype "input"))
      (node (ref "U1") (pin "4") (pinfunction "GND_4") (pintype "power_in"))
      (node (ref "U1") (pin "9") (pinfunction "EXP_9") (pintype "passive"))
      (node (ref "U2") (pin "1") (pinfunction "GND_1") (pintype "power_in"))
      (node (ref "U2") (pin "28") (pinfunction "GND_28") (pintype "power_in"))
      (node (ref "U2") (pin "29_1") (pinfunction "GND_29_1") (pintype "power_in"))
      (node (ref "U2") (pin "29_2") (pinfunction "GND_29_2") (pintype "power_in"))
      (node (ref "U2") (pin "29_3") (pinfunction "GND_29_3") (pintype "power_in"))
      (node (ref "U2") (pin "29_4") (pinfunction "GND_29_4") (pintype "power_in"))
      (node (ref "U2") (pin "29_5") (pinfunction "GND_29_5") (pintype "power_in"))
      (node (ref "U2") (pin "29_6") (pinfunction "GND_29_6") (pintype "power_in"))
      (node (ref "U2") (pin "29_7") (pinfunction "GND_29_7") (pintype "power_in"))
      (node (ref "U2") (pin "29_8") (pinfunction "GND_29_8") (pintype "power_in"))
      (node (ref "U2") (pin "29_9") (pinfunction "GND_29_9") (pintype "power_in"))
      (node (ref "U3") (pin "13") (pinfunction "GND_13") (pintype "power_in"))
      (node (ref "U4") (pin "1") (pinfunction "CTG_1") (pintype "power_in"))
      (node (ref "U4") (pin "4") (pinfunction "GND_4") (pintype "power_in"))
      (node (ref "U4") (pin "6") (pinfunction "QSTRT_6") (pintype "input"))
      (node (ref "U4") (pin "9") (pinfunction "EP_9") (pintype "power_in"))
    )
    (net (code "14") (name "GPIO8") (class "Default")
      (node (ref "R1") (pin "1") (pinfunction "1_1") (pintype "passive"))
      (node (ref "U2") (pin "10") (pinfunction "IO8_10") (pintype "bidirectional"))
    )
    (net (code "15") (name "I2C_PW") (class "Default")
      (node (ref "C1") (pin "1") (pinfunction "1_1") (pintype "passive"))
      (node (ref "C2") (pin "1") (pinfunction "1_1") (pintype "passive"))
      (node (ref "R1-PINH") (pin "2") (pinfunction "2_2") (pintype "passive"))
      (node (ref "R2-PINH") (pin "2") (pinfunction "2_2") (pintype "passive"))
      (node (ref "SENSOR2") (pin "2") (pinfunction "CSB_2") (pintype "input"))
      (node (ref "SENSOR2") (pin "6") (pinfunction "VDDIO_6") (pintype "power_in"))
      (node (ref "SENSOR2") (pin "8") (pinfunction "VDD_8") (pintype "power_in"))
      (node (ref "U2") (pin "17") (pinfunction "IO19_17") (pintype "bidirectional"))
    )
    (net (code "16") (name "INT_RTC") (class "Default")
      (node (ref "R1-PINH1") (pin "1") (pinfunction "1_1") (pintype "passive"))
      (node (ref "TP15") (pin "TP") (pinfunction "TP_TP") (pintype "input"))
      (node (ref "U2") (pin "8") (pinfunction "IO0_8") (pintype "bidirectional"))
      (node (ref "U3") (pin "3") (pinfunction "SQW/~{INT}_3") (pintype "output"))
    )
    (net (code "17") (name "IO{slash}BOOT") (class "Default")
      (node (ref "BOOT_BUTTON") (pin "3") (pinfunction "3_3") (pintype "passive"))
      (node (ref "BOOT_BUTTON") (pin "4") (pinfunction "4_4") (pintype "passive"))
      (node (ref "C6") (pin "1") (pinfunction "1_1") (pintype "passive"))
      (node (ref "R_BOOT") (pin "1") (pinfunction "1_1") (pintype "passive"))
      (node (ref "U2") (pin "15") (pinfunction "IO9_15") (pintype "bidirectional"))
    )
    (net (code "18") (name "IO{slash}CHANGE") (class "Default")
      (node (ref "C10") (pin "1") (pinfunction "1_1") (pintype "passive"))
      (node (ref "CHANGE_BUTTON") (pin "3") (pinfunction "3_3") (pintype "passive"))
      (node (ref "CHANGE_BUTTON") (pin "4") (pinfunction "4_4") (pintype "passive"))
      (node (ref "R_CHANGE") (pin "1") (pinfunction "1_1") (pintype "passive"))
      (node (ref "U2") (pin "23") (pinfunction "IO15_23") (pintype "bidirectional"))
    )
    (net (code "19") (name "MISO") (class "Default")
      (node (ref "D12") (pin "2") (pinfunction "2_2") (pintype "passive"))
      (node (ref "J4") (pin "P7") (pinfunction "DAT0_P7") (pintype "bidirectional"))
      (node (ref "R8") (pin "1") (pinfunction "1_1") (pintype "passive"))
      (node (ref "TP6") (pin "TP") (pinfunction "TP_TP") (pintype "input"))
      (node (ref "U1") (pin "2") (pinfunction "DO(IO1)_2") (pintype "bidirectional"))
      (node (ref "U2") (pin "27") (pinfunction "IO2_27") (pintype "bidirectional"))
    )
    (net (code "20") (name "MOSI") (class "Default")
      (node (ref "D11") (pin "2") (pinfunction "2_2") (pintype "passive"))
      (node (ref "J1") (pin "14") (pinfunction "14_14") (pintype "bidirectional"))
      (node (ref "J4") (pin "P3") (pinfunction "CMD_P3") (pintype "bidirectional"))
      (node (ref "R7") (pin "1") (pinfunction "1_1") (pintype "passive"))
      (node (ref "TP7") (pin "TP") (pinfunction "TP_TP") (pintype "input"))
      (node (ref "U1") (pin "5") (pinfunction "DI(IO0)_5") (pintype "bidirectional"))
      (node (ref "U2") (pin "7") (pinfunction "IO7_7") (pintype "bidirectional"))
    )
    (net (code "21") (name "Net-(CHG_LED-PadC)") (class "Default")
      (node (ref "CHG_LED") (pin "C") (pinfunction "C_C") (pintype "passive"))
      (node (ref "R1_BAT") (pin "1") (pinfunction "1_1") (pintype "passive"))
    )
    (net (code "22") (name "Net-(D2-CATHODE)") (class "Default")
      (node (ref "C1_BAT1") (pin "1") (pinfunction "1_1") (pintype "passive"))
      (node (ref "D2") (pin "1") (pinfunction "CATHODE_1") (pintype "bidirectional"))
      (node (ref "IC4") (pin "1") (pinfunction "VIN_1") (pintype "bidirectional"))
      (node (ref "IC4") (pin "3") (pinfunction "CE_3") (pintype "bidirectional"))
      (node (ref "Q1") (pin "2") (pinfunction "S_2") (pintype "bidirectional"))
    )
    (net (code "23") (name "Net-(D3-A)") (class "Default")
      (node (ref "C4") (pin "1") (pinfunction "1_1") (pintype "passive"))
      (node (ref "D3") (pin "2") (pinfunction "A_2") (pintype "bidirectional"))
      (node (ref "D4") (pin "1") (pinfunction "K_1") (pintype "bidirectional"))
    )
    (net (code "24") (name "Net-(D7-CATHODE)") (class "Default")
      (node (ref "D7") (pin "1") (pinfunction "CATHODE_1") (pintype "bidirectional"))
      (node (ref "R_CAPACITOR") (pin "1") (pinfunction "1_1") (pintype "passive"))
    )
    (net (code "25") (name "Net-(EPD_C1-Pad2)") (class "Default")
      (node (ref "EPD_C1") (pin "2") (pinfunction "2_2") (pintype "passive"))
      (node (ref "J1") (pin "4") (pinfunction "4_4") (pintype "bidirectional"))
    )
    (net (code "26") (name "Net-(EPD_C2-Pad2)") (class "Default")
      (node (ref "EPD_C2") (pin "2") (pinfunction "2_2") (pintype "passive"))
      (node (ref "J1") (pin "5") (pinfunction "5_5") (pintype "bidirectional"))
    )
    (net (code "27") (name "Net-(EPD_C6-Pad2)") (class "Default")
      (node (ref "EPD_C6") (pin "2") (pinfunction "2_2") (pintype "passive"))
      (node (ref "J1") (pin "18") (pinfunction "18_18") (pintype "bidirectional"))
    )
    (net (code "28") (name "Net-(EPD_C7-Pad2)") (class "Default")
      (node (ref "EPD_C7") (pin "2") (pinfunction "2_2") (pintype "passive"))
      (node (ref "J1") (pin "19") (pinfunction "19_19") (pintype "bidirectional"))
    )
    (net (code "29") (name "Net-(EPD_C8-Pad2)") (class "Default")
      (node (ref "EPD_C8") (pin "2") (pinfunction "2_2") (pintype "passive"))
      (node (ref "J1") (pin "20") (pinfunction "20_20") (pintype "bidirectional"))
    )
    (net (code "30") (name "Net-(EPD_C10-Pad2)") (class "Default")
      (node (ref "EPD_C10") (pin "2") (pinfunction "2_2") (pintype "passive"))
      (node (ref "J1") (pin "22") (pinfunction "22_22") (pintype "bidirectional"))
    )
    (net (code "31") (name "Net-(EPD_C12-Pad2)") (class "Default")
      (node (ref "EPD_C12") (pin "2") (pinfunction "2_2") (pintype "passive"))
      (node (ref "J1") (pin "24") (pinfunction "24_24") (pintype "bidirectional"))
    )
    (net (code "32") (name "Net-(IC1-CT)") (class "Default")
      (node (ref "C_DELAY") (pin "1") (pinfunction "1_1") (pintype "passive"))
      (node (ref "IC1") (pin "5") (pinfunction "CT_5") (pintype "bidirectional"))
    )
    (net (code "33") (name "Net-(J2-PadA5)") (class "Default")
      (node (ref "J2") (pin "A5") (pinfunction "A5_A5") (pintype "bidirectional"))
      (node (ref "R2-USB1") (pin "2") (pinfunction "2_2") (pintype "passive"))
    )
    (net (code "34") (name "Net-(J2-PadB5)") (class "Default")
      (node (ref "J2") (pin "B5") (pinfunction "B5_B5") (pintype "bidirectional"))
      (node (ref "R2-USB") (pin "1") (pinfunction "1_1") (pintype "passive"))
    )
    (net (code "35") (name "Net-(MCP73831-PROG)") (class "Default")
      (node (ref "MCP73831") (pin "5") (pinfunction "PROG_5") (pintype "input"))
      (node (ref "R2_BAT") (pin "2") (pinfunction "2_2") (pintype "passive"))
    )
    (net (code "36") (name "Net-(MCP73831-STAT)") (class "Default")
      (node (ref "MCP73831") (pin "1") (pinfunction "STAT_1") (pintype "output"))
      (node (ref "R1_BAT") (pin "2") (pinfunction "2_2") (pintype "passive"))
    )
    (net (code "37") (name "PREVGH") (class "Default")
      (node (ref "D5") (pin "1") (pinfunction "K_1") (pintype "bidirectional"))
      (node (ref "EPD_C9") (pin "2") (pinfunction "2_2") (pintype "passive"))
      (node (ref "J1") (pin "21") (pinfunction "21_21") (pintype "bidirectional"))
    )
    (net (code "38") (name "PREVGL") (class "Default")
      (node (ref "D4") (pin "2") (pinfunction "A_2") (pintype "bidirectional"))
      (node (ref "EPD_C11") (pin "2") (pinfunction "2_2") (pintype "passive"))
      (node (ref "J1") (pin "23") (pinfunction "23_23") (pintype "bidirectional"))
    )
    (net (code "39") (name "RESE") (class "Default")
      (node (ref "J1") (pin "3") (pinfunction "3_3") (pintype "bidirectional"))
      (node (ref "Q3") (pin "2") (pinfunction "S_2") (pintype "bidirectional"))
      (node (ref "R3") (pin "2") (pinfunction "2_2") (pintype "passive"))
    )
    (net (code "40") (name "RESE'") (class "Default")
      (node (ref "R2") (pin "2") (pinfunction "2_2") (pintype "passive"))
      (node (ref "R3") (pin "1") (pinfunction "1_1") (pintype "passive"))
      (node (ref "SJ1") (pin "2") (pinfunction "2_2") (pintype "passive"))
    )
    (net (code "41") (name "RESET") (class "Default")
      (node (ref "C5") (pin "1") (pinfunction "1_1") (pintype "passive"))
      (node (ref "IC1") (pin "1") (pinfunction "VOUT_1") (pintype "bidirectional"))
      (node (ref "RESET_BUTTON") (pin "3") (pinfunction "3_3") (pintype "passive"))
      (node (ref "RESET_BUTTON") (pin "4") (pinfunction "4_4") (pintype "passive"))
      (node (ref "R_RESET") (pin "1") (pinfunction "1_1") (pintype "passive"))
      (node (ref "U2") (pin "3") (pinfunction "EN_3") (pintype "input"))
    )
    (net (code "42") (name "RTC_RST") (class "Default")
      (node (ref "U2") (pin "16") (pinfunction "IO18_16") (pintype "bidirectional"))
      (node (ref "U3") (pin "4") (pinfunction "~{RST}_4") (pintype "input"))
    )
    (net (code "43") (name "RX") (class "Default")
      (node (ref "TP2") (pin "TP") (pinfunction "TP_TP") (pintype "input"))
      (node (ref "U2") (pin "24") (pinfunction "RXD0/GPIO17_24") (pintype "bidirectional"))
    )
    (net (code "44") (name "SCK") (class "Default")
      (node (ref "D10") (pin "2") (pinfunction "2_2") (pintype "passive"))
      (node (ref "J1") (pin "13") (pinfunction "13_13") (pintype "bidirectional"))
      (node (ref "J4") (pin "P5") (pinfunction "CLK_P5") (pintype "bidirectional"))
      (node (ref "R6") (pin "1") (pinfunction "1_1") (pintype "passive"))
      (node (ref "TP8") (pin "TP") (pinfunction "TP_TP") (pintype "input"))
      (node (ref "U1") (pin "6") (pinfunction "CLK_6") (pintype "input"))
      (node (ref "U2") (pin "6") (pinfunction "IO6_6") (pintype "bidirectional"))
    )
    (net (code "45") (name "SCL") (class "Default")
      (node (ref "J3") (pin "4") (pinfunction "4_4") (pintype "passive"))
      (node (ref "R2-PINH") (pin "1") (pinfunction "1_1") (pintype "passive"))
      (node (ref "SENSOR2") (pin "4") (pinfunction "SCK_4") (pintype "input"))
      (node (ref "U2") (pin "20") (pinfunction "IO22_20") (pintype "bidirectional"))
      (node (ref "U3") (pin "16") (pinfunction "SCL_16") (pintype "input"))
      (node (ref "U4") (pin "7") (pinfunction "SCL_7") (pintype "input"))
    )
    (net (code "46") (name "SDA") (class "Default")
      (node (ref "J3") (pin "3") (pinfunction "3_3") (pintype "passive"))
      (node (ref "R1-PINH") (pin "1") (pinfunction "1_1") (pintype "passive"))
      (node (ref "SENSOR2") (pin "3") (pinfunction "SDI_3") (pintype "bidirectional"))
      (node (ref "U2") (pin "19") (pinfunction "IO21_19") (pintype "bidirectional"))
      (node (ref "U3") (pin "15") (pinfunction "SDA_15") (pintype "bidirectional"))
      (node (ref "U4") (pin "8") (pinfunction "SDA_8") (pintype "bidirectional"))
    )
    (net (code "47") (name "SRC") (class "Default")
      (node (ref "C4") (pin "2") (pinfunction "2_2") (pintype "passive"))
      (node (ref "D5") (pin "2") (pinfunction "A_2") (pintype "bidirectional"))
      (node (ref "L1") (pin "1") (pinfunction "1_1") (pintype "passive"))
      (node (ref "Q3") (pin "3") (pinfunction "D_3") (pintype "bidirectional"))
    )
    (net (code "48") (name "SS_SD") (class "Default")
      (node (ref "D8") (pin "2") (pinfunction "2_2") (pintype "passive"))
      (node (ref "J4") (pin "P2") (pinfunction "CD/DAT3_P2") (pintype "bidirectional"))
      (node (ref "R10") (pin "1") (pinfunction "1_1") (pintype "passive"))
      (node (ref "U2") (pin "4") (pinfunction "IO4_4") (pintype "bidirectional"))
    )
    (net (code "49") (name "TX") (class "Default")
      (node (ref "TP1") (pin "TP") (pinfunction "TP_TP") (pintype "input"))
      (node (ref "U2") (pin "25") (pinfunction "TXD0/GPIO16_25") (pintype "bidirectional"))
    )
    (net (code "50") (name "USB_D+") (class "Default")
      (node (ref "D1") (pin "1") (pinfunction "I/O1_1_1") (pintype "bidirectional"))
      (node (ref "U2") (pin "14") (pinfunction "IO13_14") (pintype "bidirectional"))
    )
    (net (code "51") (name "USB_D-") (class "Default")
      (node (ref "D1") (pin "3") (pinfunction "I/O2_1_3") (pintype "bidirectional"))
      (node (ref "U2") (pin "13") (pinfunction "IO12_13") (pintype "bidirectional"))
    )
    (net (code "52") (name "VBAT") (class "Default")
      (node (ref "C2_BAT") (pin "1") (pinfunction "1_1") (pintype "passive"))
      (node (ref "MCP73831") (pin "3") (pinfunction "VBAT_3") (pintype "power_in"))
      (node (ref "Q1") (pin "3") (pinfunction "D_3") (pintype "bidirectional"))
      (node (ref "TP3") (pin "TP") (pinfunction "TP_TP") (pintype "input"))
      (node (ref "U4") (pin "2") (pinfunction "CELL_2") (pintype "power_in"))
      (node (ref "U4") (pin "3") (pinfunction "VDD_3") (pintype "power_in"))
    )
    (net (code "53") (name "VBUS") (class "Default")
      (node (ref "C1_BAT") (pin "1") (pinfunction "1_1") (pintype "passive"))
      (node (ref "C4_USB") (pin "1") (pinfunction "1_1") (pintype "passive"))
      (node (ref "C5_USB") (pin "1") (pinfunction "1_1") (pintype "passive"))
      (node (ref "CHG_LED") (pin "A") (pinfunction "A_A") (pintype "passive"))
      (node (ref "D1") (pin "5") (pinfunction "VBUS_5") (pintype "bidirectional"))
      (node (ref "D2") (pin "2") (pinfunction "ANODE_2") (pintype "bidirectional"))
      (node (ref "MCP73831") (pin "4") (pinfunction "VIN_4") (pintype "power_in"))
      (node (ref "PFMF.050.1") (pin "2") (pinfunction "2_2") (pintype "passive"))
      (node (ref "Q1") (pin "1") (pinfunction "G_1") (pintype "bidirectional"))
      (node (ref "R1_PWRUSB") (pin "2") (pinfunction "2_2") (pintype "passive"))
      (node (ref "TP14") (pin "TP") (pinfunction "TP_TP") (pintype "input"))
    )
    (net (code "54") (name "VRTC") (class "Default")
      (node (ref "C10_SUPERCAP") (pin "2") (pinfunction "2_2") (pintype "passive"))
      (node (ref "C8") (pin "1") (pinfunction "1_1") (pintype "passive"))
      (node (ref "R_CAPACITOR") (pin "2") (pinfunction "2_2") (pintype "passive"))
      (node (ref "U3") (pin "14") (pinfunction "VBAT_14") (pintype "power_in"))
    )
    (net (code "55") (name "VUSB") (class "Default")
      (node (ref "J2") (pin "A4") (pinfunction "A4_A4") (pintype "bidirectional"))
      (node (ref "J2") (pin "A9") (pinfunction "A9_A9") (pintype "bidirectional"))
      (node (ref "J2") (pin "B4") (pinfunction "B4_B4") (pintype "bidirectional"))
      (node (ref "J2") (pin "B9") (pinfunction "B9_B9") (pintype "bidirectional"))
      (node (ref "PFMF.050.1") (pin "1") (pinfunction "1_1") (pintype "passive"))
    )
    (net (code "56") (name "unconnected-(IC1-NC-Pad4)") (class "Default")
      (node (ref "IC1") (pin "4") (pinfunction "NC_4") (pintype "no_connect"))
    )
    (net (code "57") (name "unconnected-(IC4-NC-Pad4)") (class "Default")
      (node (ref "IC4") (pin "4") (pinfunction "NC_4") (pintype "no_connect"))
    )
    (net (code "58") (name "unconnected-(J1-Pad1)") (class "Default")
      (node (ref "J1") (pin "1") (pinfunction "1_1") (pintype "bidirectional"))
    )
    (net (code "59") (name "unconnected-(J1-Pad6)") (class "Default")
      (node (ref "J1") (pin "6") (pinfunction "6_6") (pintype "bidirectional"))
    )
    (net (code "60") (name "unconnected-(J1-Pad7)") (class "Default")
      (node (ref "J1") (pin "7") (pinfunction "7_7") (pintype "bidirectional"))
    )
    (net (code "61") (name "unconnected-(J2-PadA8)") (class "Default")
      (node (ref "J2") (pin "A8") (pinfunction "A8_A8") (pintype "bidirectional"))
    )
    (net (code "62") (name "unconnected-(J2-PadB8)") (class "Default")
      (node (ref "J2") (pin "B8") (pinfunction "B8_B8") (pintype "bidirectional"))
    )
    (net (code "63") (name "unconnected-(J4-DAT1-PadP8)") (class "Default")
      (node (ref "J4") (pin "P8") (pinfunction "DAT1_P8") (pintype "bidirectional"))
    )
    (net (code "64") (name "unconnected-(J4-DAT2-PadP1)") (class "Default")
      (node (ref "J4") (pin "P1") (pinfunction "DAT2_P1") (pintype "bidirectional"))
    )
    (net (code "65") (name "unconnected-(J4-DETECTION_1-PadS1)") (class "Default")
      (node (ref "J4") (pin "S1") (pinfunction "DETECTION_1_S1") (pintype "bidirectional"))
    )
    (net (code "66") (name "unconnected-(J4-DETECTION_2-PadS2)") (class "Default")
      (node (ref "J4") (pin "S2") (pinfunction "DETECTION_2_S2") (pintype "bidirectional"))
    )
    (net (code "67") (name "unconnected-(U2-NC-Pad22)") (class "Default")
      (node (ref "U2") (pin "22") (pinfunction "NC_22") (pintype "no_connect"))
    )
    (net (code "68") (name "unconnected-(U4-~{ALERT}-Pad5)") (class "Default")
      (node (ref "U4") (pin "5") (pinfunction "~{ALERT}_5") (pintype "output"))
    )
  )
)
